# 1_040_1573_rev01_driver.net
KiCad netlist of a schematic drawn in Altium Designer
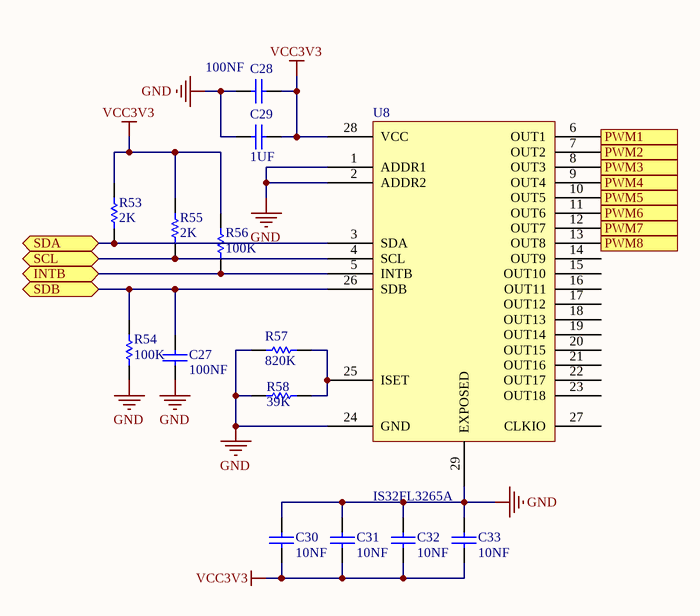
[diagram p0: 1 040 1573.rev01_driver.SchDoc]

(export (version "E")
  (design (tool "Eeschema 10.0.6"))
  (components
    (comp (ref "C27")
      (value "100NF")
      (footprint "Capacitor(0603)-1")
      (description "1 043 0098")
      (fields (field (name "PUBLISHER") "Altium Limited"))
      (libsource (lib "Sanel_Lib_V1") (part "CAP_CER_SMD_100NF_50V_0603_AEC"))
    )
    (comp (ref "C28")
      (value "100NF")
      (footprint "Capacitor(0603)-1")
      (description "1 043 0098")
      (fields (field (name "PUBLISHER") "Altium Limited"))
      (libsource (lib "Sanel_Lib_V1") (part "CAP_CER_SMD_100NF_50V_0603_AEC"))
    )
    (comp (ref "C29")
      (value "1UF")
      (footprint "Capacitor(0603)-1")
      (description "1 043 0030")
      (fields (field (name "PUBLISHER") "Altium Limited"))
      (libsource (lib "Sanel_Lib_V1") (part "CAP_CER_SMD_1UF_50V_0603_AEC"))
    )
    (comp (ref "C30")
      (value "10NF")
      (footprint "Capacitor(0603)-1")
      (description "1 043 0103")
      (fields (field (name "PUBLISHER") "Altium Limited"))
      (libsource (lib "Sanel_Lib_V1") (part "CAP_CER_SMD_10NF_50V_0603_AEC"))
    )
    (comp (ref "C31")
      (value "10NF")
      (footprint "Capacitor(0603)-1")
      (description "1 043 0103")
      (fields (field (name "PUBLISHER") "Altium Limited"))
      (libsource (lib "Sanel_Lib_V1") (part "CAP_CER_SMD_10NF_50V_0603_AEC"))
    )
    (comp (ref "C32")
      (value "10NF")
      (footprint "Capacitor(0603)-1")
      (description "1 043 0103")
      (fields (field (name "PUBLISHER") "Altium Limited"))
      (libsource (lib "Sanel_Lib_V1") (part "CAP_CER_SMD_10NF_50V_0603_AEC"))
    )
    (comp (ref "C33")
      (value "10NF")
      (footprint "Capacitor(0603)-1")
      (description "1 043 0103")
      (fields (field (name "PUBLISHER") "Altium Limited"))
      (libsource (lib "Sanel_Lib_V1") (part "CAP_CER_SMD_10NF_50V_0603_AEC"))
    )
    (comp (ref "R53")
      (value "2K")
      (footprint "Resistor(0603) -1")
      (description "1 042 0399")
      (fields (field (name "PUBLISHER") "Altium Limited"))
      (libsource (lib "Sanel_Lib_V1") (part "RES_SMD_2K_%5_0603"))
    )
    (comp (ref "R54")
      (value "100K")
      (footprint "Resistor(0603) -1")
      (description "1 042 0261")
      (fields (field (name "PUBLISHER") "Altium Limited"))
      (libsource (lib "Sanel_Lib_V1") (part "RES_SMD_100K_%1_0603_AEC"))
    )
    (comp (ref "R55")
      (value "2K")
      (footprint "Resistor(0603) -1")
      (description "1 042 0399")
      (fields (field (name "PUBLISHER") "Altium Limited"))
      (libsource (lib "Sanel_Lib_V1") (part "RES_SMD_2K_%5_0603"))
    )
    (comp (ref "R56")
      (value "100K")
      (footprint "Resistor(0603) -1")
      (description "1 042 0261")
      (fields (field (name "PUBLISHER") "Altium Limited"))
      (libsource (lib "Sanel_Lib_V1") (part "RES_SMD_100K_%1_0603_AEC"))
    )
    (comp (ref "R57")
      (value "820K")
      (footprint "Resistor(0603) -1")
      (description "1 042 0543")
      (fields (field (name "PUBLISHER") "Altium Limited"))
      (libsource (lib "Sanel_Lib_V1") (part "RES_SMD_820K_%5_0603"))
    )
    (comp (ref "R58")
      (value "39K")
      (footprint "Resistor(0603) -1")
      (description "1 042 0446")
      (fields (field (name "PUBLISHER") "Altium Limited"))
      (libsource (lib "Sanel_Lib_V1") (part "RES_SMD_39K_%5_0603"))
    )
    (comp (ref "U8")
      (value "IS32FL3265A")
      (footprint "SOP65P640X120-29N")
      (libsource (lib "Sanel_Lib") (part "IS32FL3265A"))
    )
  )
  (nets
    (net (code "1") (name "/INTB") (class "Default")
      (node (ref "R56") (pin "1") (pinfunction "1_1") (pintype "passive"))
      (node (ref "U8") (pin "5") (pinfunction "INTB_5") (pintype "passive"))
    )
    (net (code "2") (name "/PWM1") (class "Default")
      (node (ref "U8") (pin "6") (pinfunction "OUT1_6") (pintype "passive"))
    )
    (net (code "3") (name "/PWM2") (class "Default")
      (node (ref "U8") (pin "7") (pinfunction "OUT2_7") (pintype "passive"))
    )
    (net (code "4") (name "/PWM3") (class "Default")
      (node (ref "U8") (pin "8") (pinfunction "OUT3_8") (pintype "passive"))
    )
    (net (code "5") (name "/PWM4") (class "Default")
      (node (ref "U8") (pin "9") (pinfunction "OUT4_9") (pintype "passive"))
    )
    (net (code "6") (name "/PWM5") (class "Default")
      (node (ref "U8") (pin "10") (pinfunction "OUT5_10") (pintype "passive"))
    )
    (net (code "7") (name "/PWM6") (class "Default")
      (node (ref "U8") (pin "11") (pinfunction "OUT6_11") (pintype "passive"))
    )
    (net (code "8") (name "/PWM7") (class "Default")
      (node (ref "U8") (pin "12") (pinfunction "OUT7_12") (pintype "passive"))
    )
    (net (code "9") (name "/PWM8") (class "Default")
      (node (ref "U8") (pin "13") (pinfunction "OUT8_13") (pintype "passive"))
    )
    (net (code "10") (name "/SCL") (class "Default")
      (node (ref "R55") (pin "1") (pinfunction "1_1") (pintype "passive"))
      (node (ref "U8") (pin "4") (pinfunction "SCL_4") (pintype "passive"))
    )
    (net (code "11") (name "/SDA") (class "Default")
      (node (ref "R53") (pin "1") (pinfunction "1_1") (pintype "passive"))
      (node (ref "U8") (pin "3") (pinfunction "SDA_3") (pintype "passive"))
    )
    (net (code "12") (name "/SDB") (class "Default")
      (node (ref "C27") (pin "2") (pinfunction "2_2") (pintype "passive"))
      (node (ref "R54") (pin "2") (pinfunction "2_2") (pintype "passive"))
      (node (ref "U8") (pin "26") (pinfunction "SDB_26") (pintype "passive"))
    )
    (net (code "13") (name "GND") (class "Default")
      (node (ref "C27") (pin "1") (pinfunction "1_1") (pintype "passive"))
      (node (ref "C28") (pin "1") (pinfunction "1_1") (pintype "passive"))
      (node (ref "C29") (pin "2") (pinfunction "2_2") (pintype "passive"))
      (node (ref "C30") (pin "1") (pinfunction "1_1") (pintype "passive"))
      (node (ref "C31") (pin "1") (pinfunction "1_1") (pintype "passive"))
      (node (ref "C32") (pin "1") (pinfunction "1_1") (pintype "passive"))
      (node (ref "C33") (pin "1") (pinfunction "1_1") (pintype "passive"))
      (node (ref "R54") (pin "1") (pinfunction "1_1") (pintype "passive"))
      (node (ref "R57") (pin "1") (pinfunction "1_1") (pintype "passive"))
      (node (ref "R58") (pin "1") (pinfunction "1_1") (pintype "passive"))
      (node (ref "U8") (pin "1") (pinfunction "ADDR1_1") (pintype "passive"))
      (node (ref "U8") (pin "2") (pinfunction "ADDR2_2") (pintype "passive"))
      (node (ref "U8") (pin "24") (pinfunction "GND_24") (pintype "passive"))
      (node (ref "U8") (pin "29") (pinfunction "EXPOSED_29") (pintype "passive"))
    )
    (net (code "14") (name "Net-(U8-ISET)") (class "Default")
      (node (ref "R57") (pin "2") (pinfunction "2_2") (pintype "passive"))
      (node (ref "R58") (pin "2") (pinfunction "2_2") (pintype "passive"))
      (node (ref "U8") (pin "25") (pinfunction "ISET_25") (pintype "passive"))
    )
    (net (code "15") (name "VCC3V3") (class "Default")
      (node (ref "C28") (pin "2") (pinfunction "2_2") (pintype "passive"))
      (node (ref "C29") (pin "1") (pinfunction "1_1") (pintype "passive"))
      (node (ref "C30") (pin "2") (pinfunction "2_2") (pintype "passive"))
      (node (ref "C31") (pin "2") (pinfunction "2_2") (pintype "passive"))
      (node (ref "C32") (pin "2") (pinfunction "2_2") (pintype "passive"))
      (node (ref "C33") (pin "2") (pinfunction "2_2") (pintype "passive"))
      (node (ref "R53") (pin "2") (pinfunction "2_2") (pintype "passive"))
      (node (ref "R55") (pin "2") (pinfunction "2_2") (pintype "passive"))
      (node (ref "R56") (pin "2") (pinfunction "2_2") (pintype "passive"))
      (node (ref "U8") (pin "28") (pinfunction "VCC_28") (pintype "passive"))
    )
    (net (code "16") (name "unconnected-(U8-CLKIO-Pad27)") (class "Default")
      (node (ref "U8") (pin "27") (pinfunction "CLKIO_27") (pintype "passive"))
    )
    (net (code "17") (name "unconnected-(U8-OUT9-Pad14)") (class "Default")
      (node (ref "U8") (pin "14") (pinfunction "OUT9_14") (pintype "passive"))
    )
    (net (code "18") (name "unconnected-(U8-OUT10-Pad15)") (class "Default")
      (node (ref "U8") (pin "15") (pinfunction "OUT10_15") (pintype "passive"))
    )
    (net (code "19") (name "unconnected-(U8-OUT11-Pad16)") (class "Default")
      (node (ref "U8") (pin "16") (pinfunction "OUT11_16") (pintype "passive"))
    )
    (net (code "20") (name "unconnected-(U8-OUT12-Pad17)") (class "Default")
      (node (ref "U8") (pin "17") (pinfunction "OUT12_17") (pintype "passive"))
    )
    (net (code "21") (name "unconnected-(U8-OUT13-Pad18)") (class "Default")
      (node (ref "U8") (pin "18") (pinfunction "OUT13_18") (pintype "passive"))
    )
    (net (code "22") (name "unconnected-(U8-OUT14-Pad19)") (class "Default")
      (node (ref "U8") (pin "19") (pinfunction "OUT14_19") (pintype "passive"))
    )
    (net (code "23") (name "unconnected-(U8-OUT15-Pad20)") (class "Default")
      (node (ref "U8") (pin "20") (pinfunction "OUT15_20") (pintype "passive"))
    )
    (net (code "24") (name "unconnected-(U8-OUT16-Pad21)") (class "Default")
      (node (ref "U8") (pin "21") (pinfunction "OUT16_21") (pintype "passive"))
    )
    (net (code "25") (name "unconnected-(U8-OUT17-Pad22)") (class "Default")
      (node (ref "U8") (pin "22") (pinfunction "OUT17_22") (pintype "passive"))
    )
    (net (code "26") (name "unconnected-(U8-OUT18-Pad23)") (class "Default")
      (node (ref "U8") (pin "23") (pinfunction "OUT18_23") (pintype "passive"))
    )
  )
)
